# SparkFun_Shift_Register_Breakout-74HC595.net
KiCad netlist of a schematic drawn in EAGLE
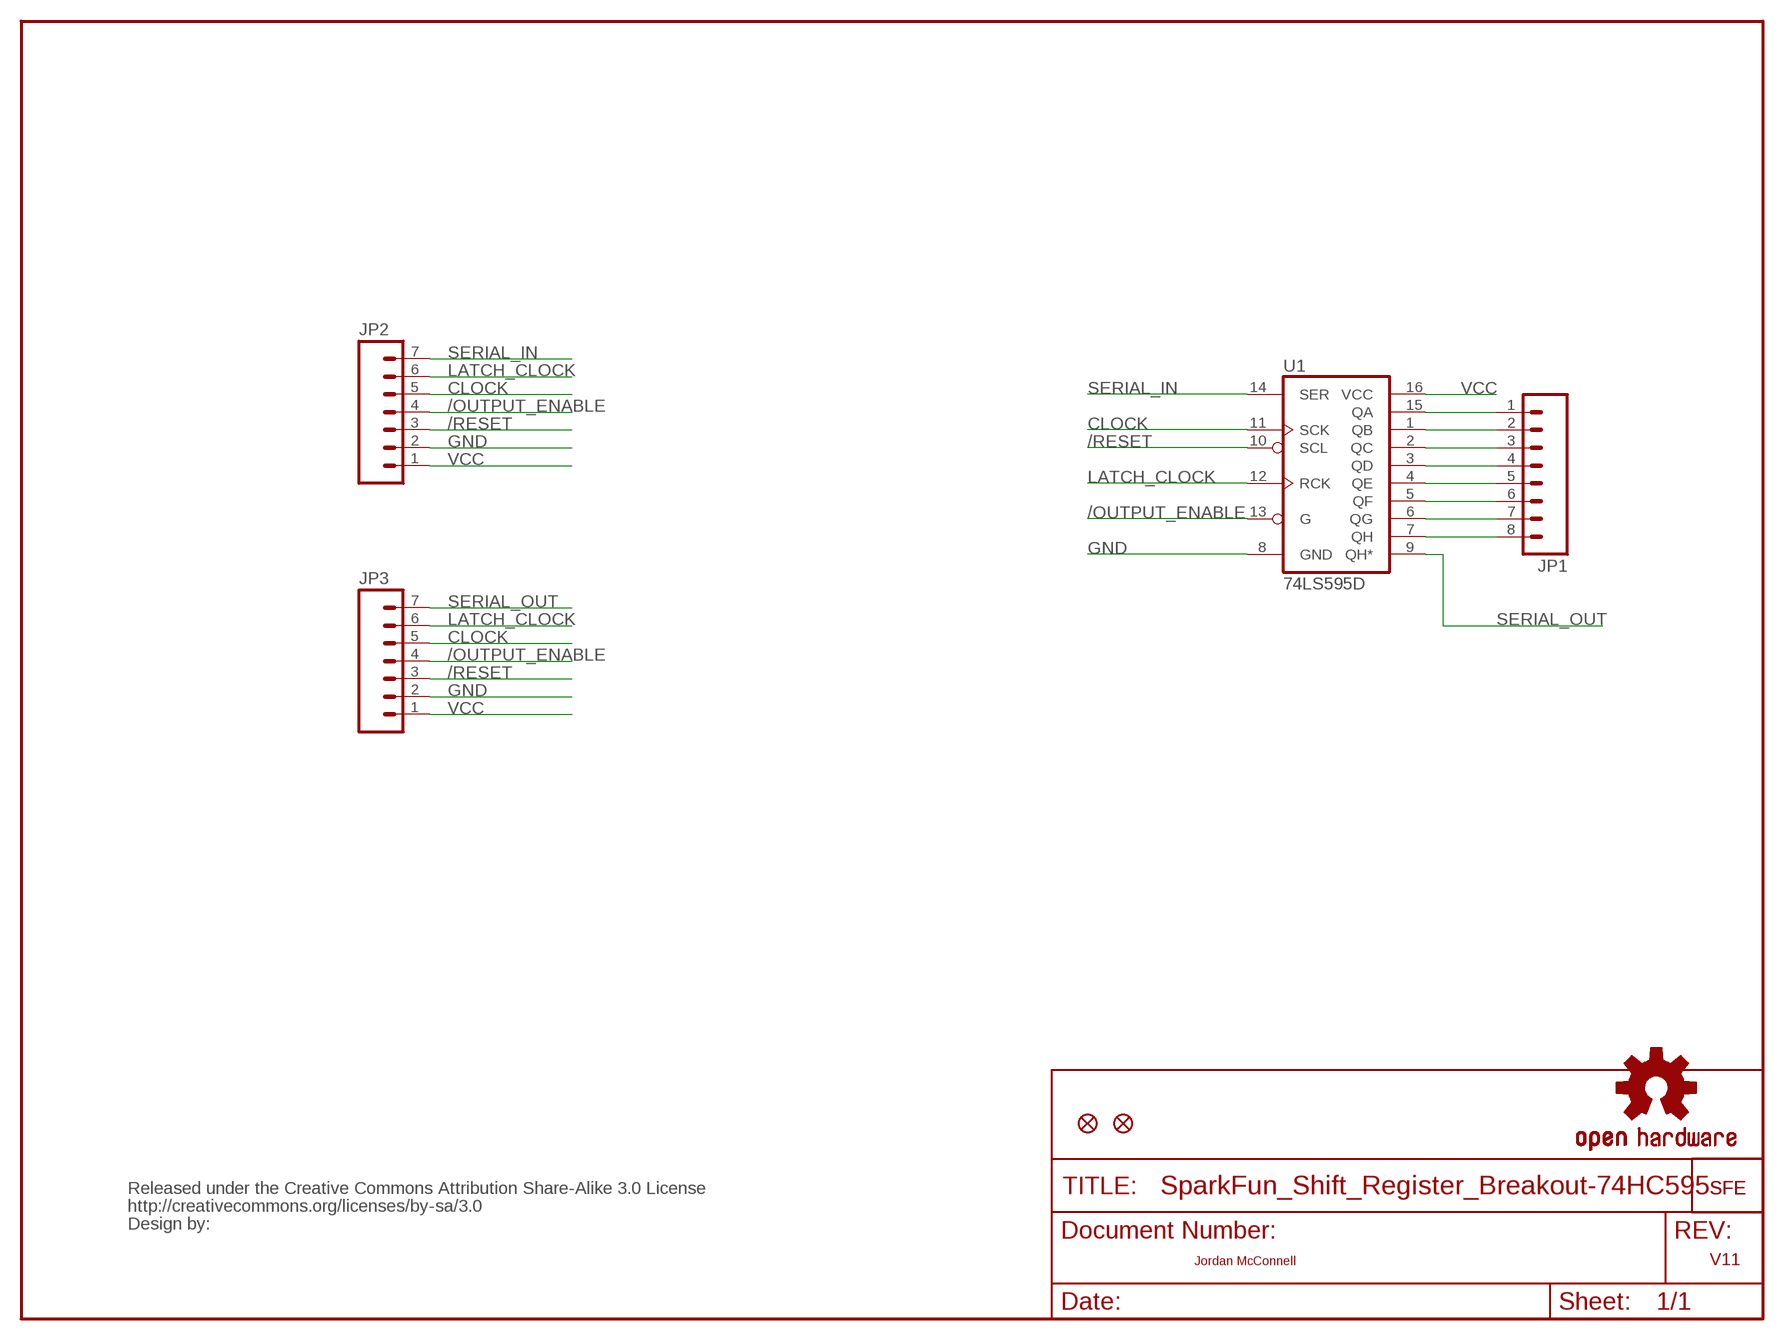
[diagram p0: schematic, sheet 1]

(export (version "E")
  (design (tool "Eeschema 10.0.6"))
  (components
    (comp (ref "JP1")
      (value "M08")
      (footprint "eagle-import:1X08")
      (libsource (lib "eagle-import") (part "M08"))
    )
    (comp (ref "JP2")
      (value "M07")
      (footprint "eagle-import:1X07")
      (libsource (lib "eagle-import") (part "M07"))
    )
    (comp (ref "JP3")
      (value "M07")
      (footprint "eagle-import:1X07")
      (libsource (lib "eagle-import") (part "M07"))
    )
    (comp (ref "JP4")
      (value "LOGO-SFENEW")
      (footprint "eagle-import:SFE-NEW-WEBLOGO")
      (libsource (lib "eagle-import") (part "LOGO-SFENEW"))
    )
    (comp (ref "JP5")
      (value "LOGO-SFESK")
      (footprint "eagle-import:SFE-LOGO-FLAME")
      (libsource (lib "eagle-import") (part "LOGO-SFESK"))
    )
    (comp (ref "JP6")
      (value "FIDUCIAL1X2.5")
      (footprint "eagle-import:FIDUCIAL-1X2.5")
      (libsource (lib "eagle-import") (part "FIDUCIAL1X2.5"))
    )
    (comp (ref "JP7")
      (value "FIDUCIAL1X2.5")
      (footprint "eagle-import:FIDUCIAL-1X2.5")
      (libsource (lib "eagle-import") (part "FIDUCIAL1X2.5"))
    )
    (comp (ref "U$1")
      (value "OSHW-LOGOM")
      (footprint "eagle-import:OSHW-LOGO-M")
      (libsource (lib "eagle-import") (part "OSHW-LOGOM"))
    )
    (comp (ref "U$2")
      (value "CREATIVE_COMMONS")
      (footprint "eagle-import:CREATIVE_COMMONS")
      (libsource (lib "eagle-import") (part "CREATIVE_COMMONS"))
    )
    (comp (ref "U1")
      (value "74LS595D")
      (footprint "eagle-import:SO16")
      (libsource (lib "eagle-import") (part "74595DLS"))
    )
  )
  (nets
    (net (code "1") (name "/CLOCK") (class "Default")
      (node (ref "JP2") (pin "5") (pinfunction "5_5") (pintype "passive"))
      (node (ref "JP3") (pin "5") (pinfunction "5_5") (pintype "passive"))
      (node (ref "U1") (pin "11") (pinfunction "SCK_11") (pintype "input"))
    )
    (net (code "2") (name "/GND") (class "Default")
      (node (ref "JP2") (pin "2") (pinfunction "2_2") (pintype "passive"))
      (node (ref "JP3") (pin "2") (pinfunction "2_2") (pintype "passive"))
      (node (ref "U1") (pin "8") (pinfunction "GND_8") (pintype "power_in"))
    )
    (net (code "3") (name "/LATCH_CLOCK") (class "Default")
      (node (ref "JP2") (pin "6") (pinfunction "6_6") (pintype "passive"))
      (node (ref "JP3") (pin "6") (pinfunction "6_6") (pintype "passive"))
      (node (ref "U1") (pin "12") (pinfunction "RCK_12") (pintype "input"))
    )
    (net (code "4") (name "/SERIAL_IN") (class "Default")
      (node (ref "JP2") (pin "7") (pinfunction "7_7") (pintype "passive"))
      (node (ref "U1") (pin "14") (pinfunction "SER_14") (pintype "input"))
    )
    (net (code "5") (name "/SERIAL_OUT") (class "Default")
      (node (ref "JP3") (pin "7") (pinfunction "7_7") (pintype "passive"))
      (node (ref "U1") (pin "9") (pinfunction "QH*_9") (pintype "tri_state"))
    )
    (net (code "6") (name "/VCC") (class "Default")
      (node (ref "JP2") (pin "1") (pinfunction "1_1") (pintype "passive"))
      (node (ref "JP3") (pin "1") (pinfunction "1_1") (pintype "passive"))
      (node (ref "U1") (pin "16") (pinfunction "VCC_16") (pintype "power_in"))
    )
    (net (code "7") (name "/{slash}OUTPUT_ENABLE") (class "Default")
      (node (ref "JP2") (pin "4") (pinfunction "4_4") (pintype "passive"))
      (node (ref "JP3") (pin "4") (pinfunction "4_4") (pintype "passive"))
      (node (ref "U1") (pin "13") (pinfunction "G_13") (pintype "input"))
    )
    (net (code "8") (name "/{slash}RESET") (class "Default")
      (node (ref "JP2") (pin "3") (pinfunction "3_3") (pintype "passive"))
      (node (ref "JP3") (pin "3") (pinfunction "3_3") (pintype "passive"))
      (node (ref "U1") (pin "10") (pinfunction "SCL_10") (pintype "input"))
    )
    (net (code "9") (name "Net-(U1-QA)") (class "Default")
      (node (ref "JP1") (pin "1") (pinfunction "1_1") (pintype "passive"))
      (node (ref "U1") (pin "15") (pinfunction "QA_15") (pintype "tri_state"))
    )
    (net (code "10") (name "Net-(U1-QB)") (class "Default")
      (node (ref "JP1") (pin "2") (pinfunction "2_2") (pintype "passive"))
      (node (ref "U1") (pin "1") (pinfunction "QB_1") (pintype "tri_state"))
    )
    (net (code "11") (name "Net-(U1-QC)") (class "Default")
      (node (ref "JP1") (pin "3") (pinfunction "3_3") (pintype "passive"))
      (node (ref "U1") (pin "2") (pinfunction "QC_2") (pintype "tri_state"))
    )
    (net (code "12") (name "Net-(U1-QD)") (class "Default")
      (node (ref "JP1") (pin "4") (pinfunction "4_4") (pintype "passive"))
      (node (ref "U1") (pin "3") (pinfunction "QD_3") (pintype "tri_state"))
    )
    (net (code "13") (name "Net-(U1-QE)") (class "Default")
      (node (ref "JP1") (pin "5") (pinfunction "5_5") (pintype "passive"))
      (node (ref "U1") (pin "4") (pinfunction "QE_4") (pintype "tri_state"))
    )
    (net (code "14") (name "Net-(U1-QF)") (class "Default")
      (node (ref "JP1") (pin "6") (pinfunction "6_6") (pintype "passive"))
      (node (ref "U1") (pin "5") (pinfunction "QF_5") (pintype "tri_state"))
    )
    (net (code "15") (name "Net-(U1-QG)") (class "Default")
      (node (ref "JP1") (pin "7") (pinfunction "7_7") (pintype "passive"))
      (node (ref "U1") (pin "6") (pinfunction "QG_6") (pintype "tri_state"))
    )
    (net (code "16") (name "Net-(U1-QH)") (class "Default")
      (node (ref "JP1") (pin "8") (pinfunction "8_8") (pintype "passive"))
      (node (ref "U1") (pin "7") (pinfunction "QH_7") (pintype "tri_state"))
    )
  )
)
